# IO.net
KiCad netlist of a schematic drawn in Altium Designer
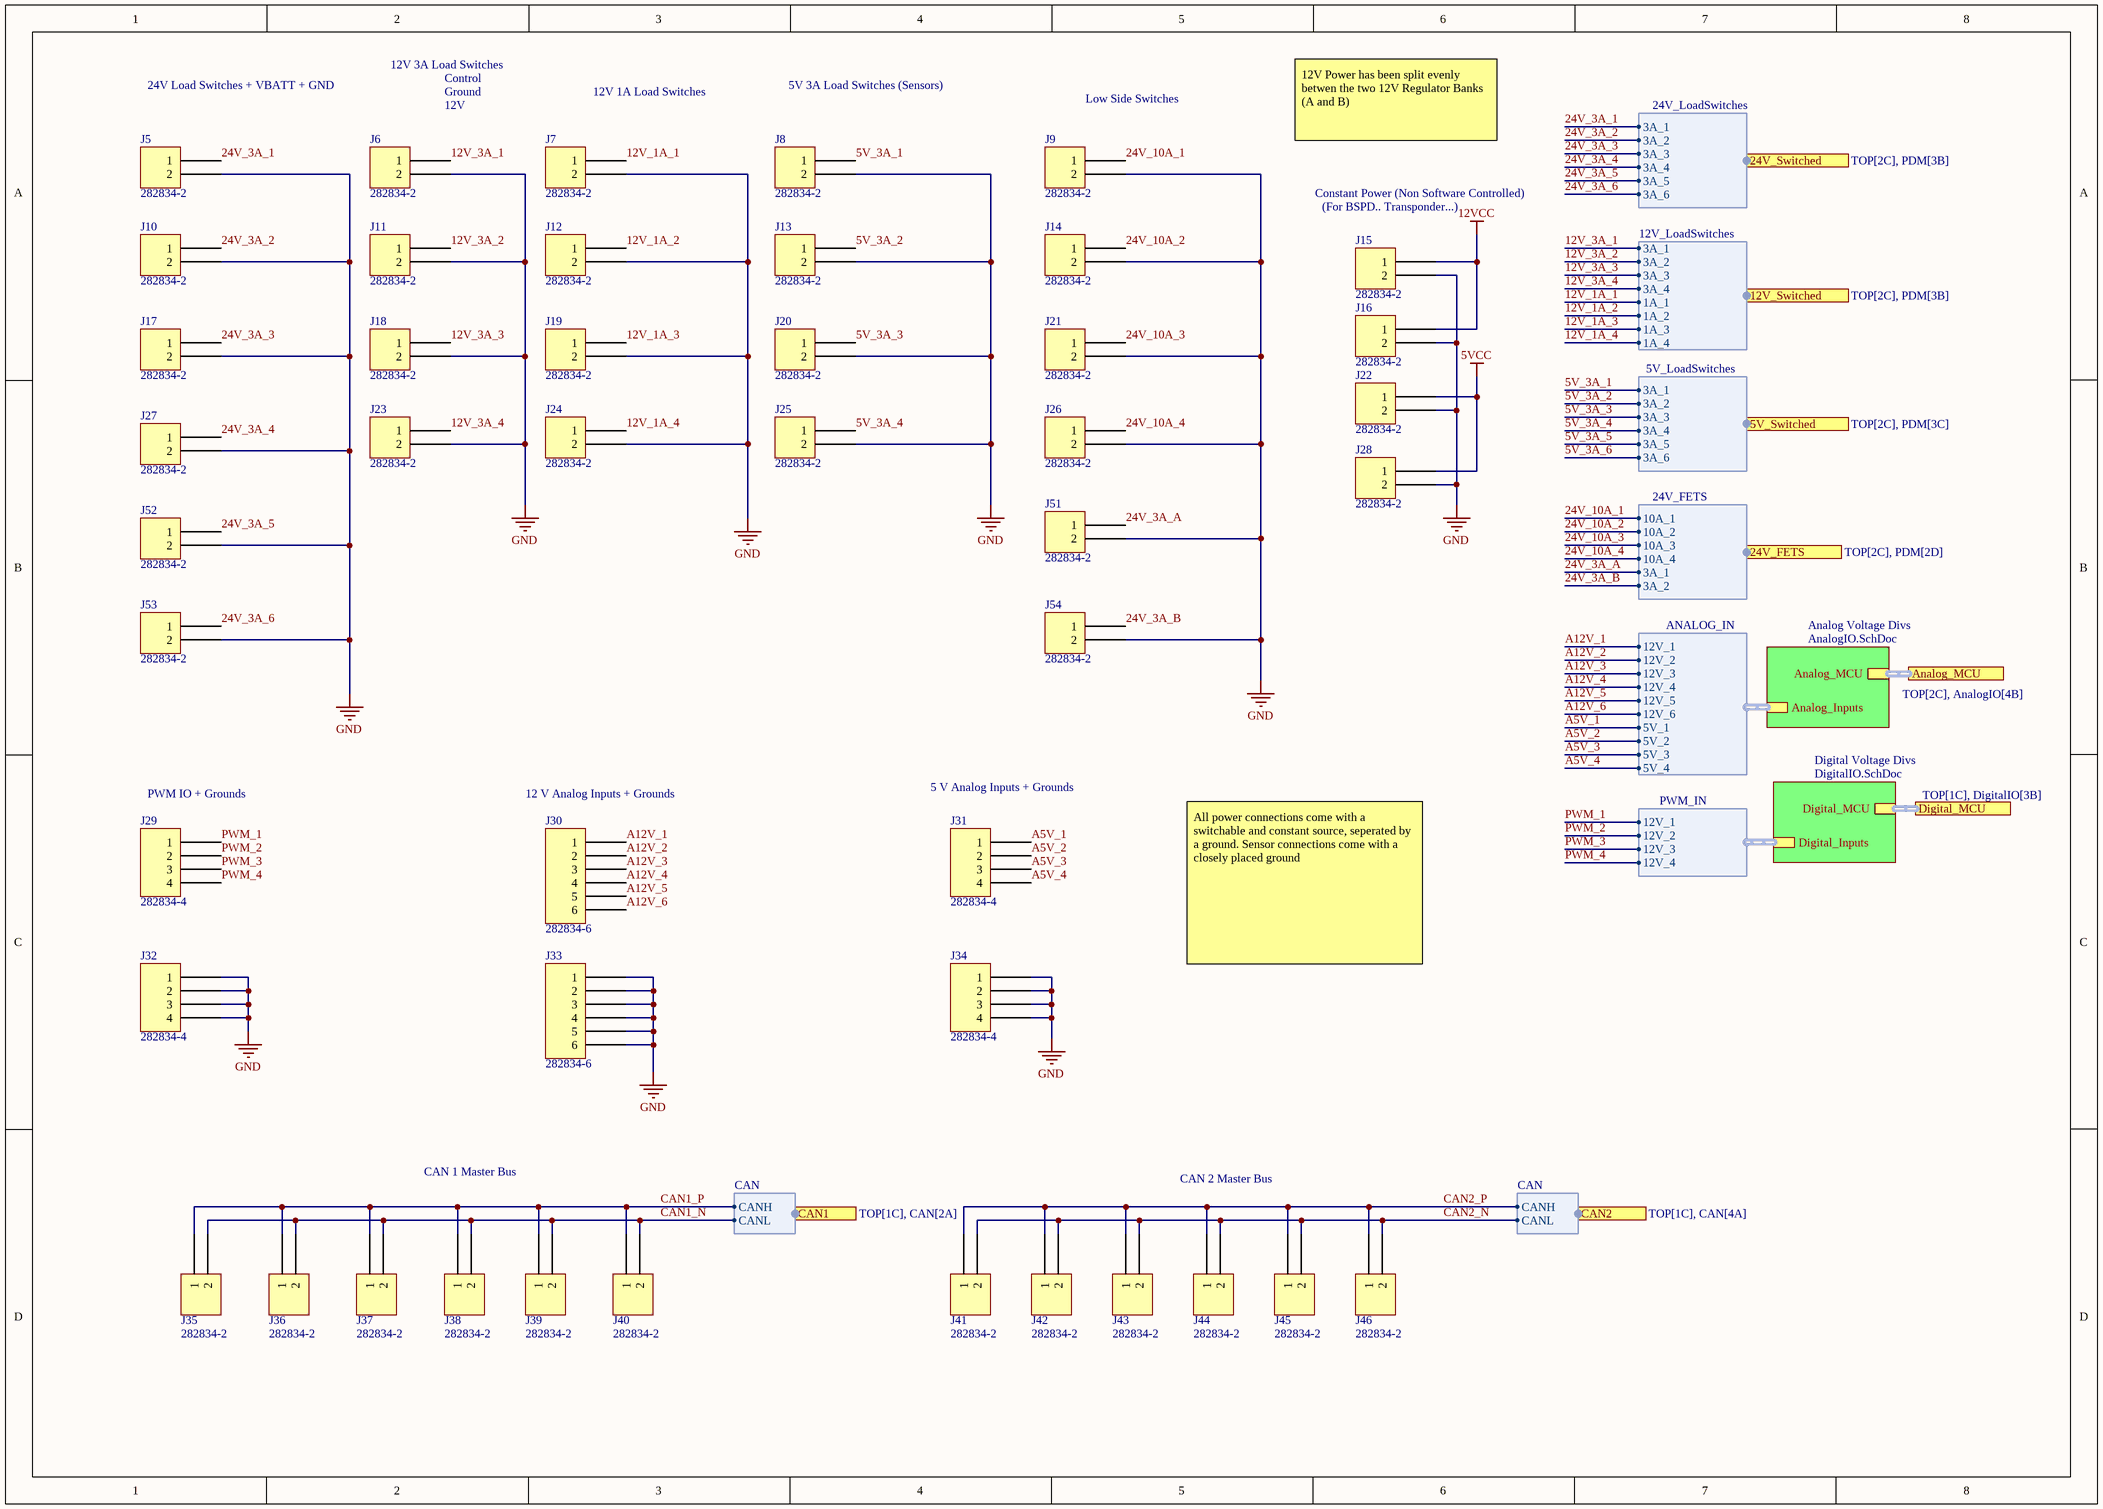
[diagram p0: IO.SchDoc]

(export (version "E")
  (design (tool "Eeschema 10.0.6"))
  (components
    (comp (ref "J5")
      (value "282834-2")
      (footprint "TE 282834-2")
      (description "TERM BLK 2P SIDE ENT 2.54MM PCB")
      (libsource (lib "altium_library") (part "2 Pin"))
    )
    (comp (ref "J6")
      (value "282834-2")
      (footprint "TE 282834-2")
      (description "TERM BLK 2P SIDE ENT 2.54MM PCB")
      (libsource (lib "altium_library") (part "2 Pin"))
    )
    (comp (ref "J7")
      (value "282834-2")
      (footprint "TE 282834-2")
      (description "TERM BLK 2P SIDE ENT 2.54MM PCB")
      (libsource (lib "altium_library") (part "2 Pin"))
    )
    (comp (ref "J8")
      (value "282834-2")
      (footprint "TE 282834-2")
      (description "TERM BLK 2P SIDE ENT 2.54MM PCB")
      (libsource (lib "altium_library") (part "2 Pin"))
    )
    (comp (ref "J9")
      (value "282834-2")
      (footprint "TE 282834-2")
      (description "TERM BLK 2P SIDE ENT 2.54MM PCB")
      (libsource (lib "altium_library") (part "2 Pin"))
    )
    (comp (ref "J10")
      (value "282834-2")
      (footprint "TE 282834-2")
      (description "TERM BLK 2P SIDE ENT 2.54MM PCB")
      (libsource (lib "altium_library") (part "2 Pin"))
    )
    (comp (ref "J11")
      (value "282834-2")
      (footprint "TE 282834-2")
      (description "TERM BLK 2P SIDE ENT 2.54MM PCB")
      (libsource (lib "altium_library") (part "2 Pin"))
    )
    (comp (ref "J12")
      (value "282834-2")
      (footprint "TE 282834-2")
      (description "TERM BLK 2P SIDE ENT 2.54MM PCB")
      (libsource (lib "altium_library") (part "2 Pin"))
    )
    (comp (ref "J13")
      (value "282834-2")
      (footprint "TE 282834-2")
      (description "TERM BLK 2P SIDE ENT 2.54MM PCB")
      (libsource (lib "altium_library") (part "2 Pin"))
    )
    (comp (ref "J14")
      (value "282834-2")
      (footprint "TE 282834-2")
      (description "TERM BLK 2P SIDE ENT 2.54MM PCB")
      (libsource (lib "altium_library") (part "2 Pin"))
    )
    (comp (ref "J15")
      (value "282834-2")
      (footprint "TE 282834-2")
      (description "TERM BLK 2P SIDE ENT 2.54MM PCB")
      (libsource (lib "altium_library") (part "2 Pin"))
    )
    (comp (ref "J16")
      (value "282834-2")
      (footprint "TE 282834-2")
      (description "TERM BLK 2P SIDE ENT 2.54MM PCB")
      (libsource (lib "altium_library") (part "2 Pin"))
    )
    (comp (ref "J17")
      (value "282834-2")
      (footprint "TE 282834-2")
      (description "TERM BLK 2P SIDE ENT 2.54MM PCB")
      (libsource (lib "altium_library") (part "2 Pin"))
    )
    (comp (ref "J18")
      (value "282834-2")
      (footprint "TE 282834-2")
      (description "TERM BLK 2P SIDE ENT 2.54MM PCB")
      (libsource (lib "altium_library") (part "2 Pin"))
    )
    (comp (ref "J19")
      (value "282834-2")
      (footprint "TE 282834-2")
      (description "TERM BLK 2P SIDE ENT 2.54MM PCB")
      (libsource (lib "altium_library") (part "2 Pin"))
    )
    (comp (ref "J20")
      (value "282834-2")
      (footprint "TE 282834-2")
      (description "TERM BLK 2P SIDE ENT 2.54MM PCB")
      (libsource (lib "altium_library") (part "2 Pin"))
    )
    (comp (ref "J21")
      (value "282834-2")
      (footprint "TE 282834-2")
      (description "TERM BLK 2P SIDE ENT 2.54MM PCB")
      (libsource (lib "altium_library") (part "2 Pin"))
    )
    (comp (ref "J22")
      (value "282834-2")
      (footprint "TE 282834-2")
      (description "TERM BLK 2P SIDE ENT 2.54MM PCB")
      (libsource (lib "altium_library") (part "2 Pin"))
    )
    (comp (ref "J23")
      (value "282834-2")
      (footprint "TE 282834-2")
      (description "TERM BLK 2P SIDE ENT 2.54MM PCB")
      (libsource (lib "altium_library") (part "2 Pin"))
    )
    (comp (ref "J24")
      (value "282834-2")
      (footprint "TE 282834-2")
      (description "TERM BLK 2P SIDE ENT 2.54MM PCB")
      (libsource (lib "altium_library") (part "2 Pin"))
    )
    (comp (ref "J25")
      (value "282834-2")
      (footprint "TE 282834-2")
      (description "TERM BLK 2P SIDE ENT 2.54MM PCB")
      (libsource (lib "altium_library") (part "2 Pin"))
    )
    (comp (ref "J26")
      (value "282834-2")
      (footprint "TE 282834-2")
      (description "TERM BLK 2P SIDE ENT 2.54MM PCB")
      (libsource (lib "altium_library") (part "2 Pin"))
    )
    (comp (ref "J27")
      (value "282834-2")
      (footprint "TE 282834-2")
      (description "TERM BLK 2P SIDE ENT 2.54MM PCB")
      (libsource (lib "altium_library") (part "2 Pin"))
    )
    (comp (ref "J28")
      (value "282834-2")
      (footprint "TE 282834-2")
      (description "TERM BLK 2P SIDE ENT 2.54MM PCB")
      (libsource (lib "altium_library") (part "2 Pin"))
    )
    (comp (ref "J29")
      (value "282834-4")
      (footprint "TE 282834-4")
      (description "TERM BLK 4P SIDE ENT 2.54MM PCB")
      (libsource (lib "altium_library") (part "4 Pin"))
    )
    (comp (ref "J30")
      (value "282834-6")
      (footprint "TE 282834-6")
      (description "TERM BLK 6P SIDE ENT 2.54MM PCB")
      (libsource (lib "altium_library") (part "6 Pin"))
    )
    (comp (ref "J31")
      (value "282834-4")
      (footprint "TE 282834-4")
      (description "TERM BLK 4P SIDE ENT 2.54MM PCB")
      (libsource (lib "altium_library") (part "4 Pin"))
    )
    (comp (ref "J32")
      (value "282834-4")
      (footprint "TE 282834-4")
      (description "TERM BLK 4P SIDE ENT 2.54MM PCB")
      (libsource (lib "altium_library") (part "4 Pin"))
    )
    (comp (ref "J33")
      (value "282834-6")
      (footprint "TE 282834-6")
      (description "TERM BLK 6P SIDE ENT 2.54MM PCB")
      (libsource (lib "altium_library") (part "6 Pin"))
    )
    (comp (ref "J34")
      (value "282834-4")
      (footprint "TE 282834-4")
      (description "TERM BLK 4P SIDE ENT 2.54MM PCB")
      (libsource (lib "altium_library") (part "4 Pin"))
    )
    (comp (ref "J35")
      (value "282834-2")
      (footprint "TE 282834-2")
      (description "TERM BLK 2P SIDE ENT 2.54MM PCB")
      (libsource (lib "") (part "2 Pin_1"))
    )
    (comp (ref "J36")
      (value "282834-2")
      (footprint "TE 282834-2")
      (description "TERM BLK 2P SIDE ENT 2.54MM PCB")
      (libsource (lib "") (part "2 Pin_1"))
    )
    (comp (ref "J37")
      (value "282834-2")
      (footprint "TE 282834-2")
      (description "TERM BLK 2P SIDE ENT 2.54MM PCB")
      (libsource (lib "") (part "2 Pin_1"))
    )
    (comp (ref "J38")
      (value "282834-2")
      (footprint "TE 282834-2")
      (description "TERM BLK 2P SIDE ENT 2.54MM PCB")
      (libsource (lib "") (part "2 Pin_1"))
    )
    (comp (ref "J39")
      (value "282834-2")
      (footprint "TE 282834-2")
      (description "TERM BLK 2P SIDE ENT 2.54MM PCB")
      (libsource (lib "") (part "2 Pin_1"))
    )
    (comp (ref "J40")
      (value "282834-2")
      (footprint "TE 282834-2")
      (description "TERM BLK 2P SIDE ENT 2.54MM PCB")
      (libsource (lib "") (part "2 Pin_1"))
    )
    (comp (ref "J41")
      (value "282834-2")
      (footprint "TE 282834-2")
      (description "TERM BLK 2P SIDE ENT 2.54MM PCB")
      (libsource (lib "") (part "2 Pin_1"))
    )
    (comp (ref "J42")
      (value "282834-2")
      (footprint "TE 282834-2")
      (description "TERM BLK 2P SIDE ENT 2.54MM PCB")
      (libsource (lib "") (part "2 Pin_1"))
    )
    (comp (ref "J43")
      (value "282834-2")
      (footprint "TE 282834-2")
      (description "TERM BLK 2P SIDE ENT 2.54MM PCB")
      (libsource (lib "") (part "2 Pin_1"))
    )
    (comp (ref "J44")
      (value "282834-2")
      (footprint "TE 282834-2")
      (description "TERM BLK 2P SIDE ENT 2.54MM PCB")
      (libsource (lib "") (part "2 Pin_1"))
    )
    (comp (ref "J45")
      (value "282834-2")
      (footprint "TE 282834-2")
      (description "TERM BLK 2P SIDE ENT 2.54MM PCB")
      (libsource (lib "") (part "2 Pin_1"))
    )
    (comp (ref "J46")
      (value "282834-2")
      (footprint "TE 282834-2")
      (description "TERM BLK 2P SIDE ENT 2.54MM PCB")
      (libsource (lib "") (part "2 Pin_1"))
    )
    (comp (ref "J51")
      (value "282834-2")
      (footprint "TE 282834-2")
      (description "TERM BLK 2P SIDE ENT 2.54MM PCB")
      (libsource (lib "altium_library") (part "2 Pin"))
    )
    (comp (ref "J52")
      (value "282834-2")
      (footprint "TE 282834-2")
      (description "TERM BLK 2P SIDE ENT 2.54MM PCB")
      (libsource (lib "altium_library") (part "2 Pin"))
    )
    (comp (ref "J53")
      (value "282834-2")
      (footprint "TE 282834-2")
      (description "TERM BLK 2P SIDE ENT 2.54MM PCB")
      (libsource (lib "altium_library") (part "2 Pin"))
    )
    (comp (ref "J54")
      (value "282834-2")
      (footprint "TE 282834-2")
      (description "TERM BLK 2P SIDE ENT 2.54MM PCB")
      (libsource (lib "altium_library") (part "2 Pin"))
    )
  )
  (nets
    (net (code "10") (name "/5V_3A_1") (class "Default")
      (node (ref "J8") (pin "1") (pinfunction "1_1") (pintype "passive"))
    )
    (net (code "11") (name "/5V_3A_2") (class "Default")
      (node (ref "J13") (pin "1") (pinfunction "1_1") (pintype "passive"))
    )
    (net (code "12") (name "/5V_3A_3") (class "Default")
      (node (ref "J20") (pin "1") (pinfunction "1_1") (pintype "passive"))
    )
    (net (code "13") (name "/5V_3A_4") (class "Default")
      (node (ref "J25") (pin "1") (pinfunction "1_1") (pintype "passive"))
    )
    (net (code "16") (name "/12V_1A_1") (class "Default")
      (node (ref "J7") (pin "1") (pinfunction "1_1") (pintype "passive"))
    )
    (net (code "17") (name "/12V_1A_2") (class "Default")
      (node (ref "J12") (pin "1") (pinfunction "1_1") (pintype "passive"))
    )
    (net (code "18") (name "/12V_1A_3") (class "Default")
      (node (ref "J19") (pin "1") (pinfunction "1_1") (pintype "passive"))
    )
    (net (code "19") (name "/12V_1A_4") (class "Default")
      (node (ref "J24") (pin "1") (pinfunction "1_1") (pintype "passive"))
    )
    (net (code "20") (name "/12V_3A_1") (class "Default")
      (node (ref "J6") (pin "1") (pinfunction "1_1") (pintype "passive"))
    )
    (net (code "21") (name "/12V_3A_2") (class "Default")
      (node (ref "J11") (pin "1") (pinfunction "1_1") (pintype "passive"))
    )
    (net (code "22") (name "/12V_3A_3") (class "Default")
      (node (ref "J18") (pin "1") (pinfunction "1_1") (pintype "passive"))
    )
    (net (code "23") (name "/12V_3A_4") (class "Default")
      (node (ref "J23") (pin "1") (pinfunction "1_1") (pintype "passive"))
    )
    (net (code "24") (name "/24V_3A_1") (class "Default")
      (node (ref "J5") (pin "1") (pinfunction "1_1") (pintype "passive"))
    )
    (net (code "25") (name "/24V_3A_2") (class "Default")
      (node (ref "J10") (pin "1") (pinfunction "1_1") (pintype "passive"))
    )
    (net (code "26") (name "/24V_3A_3") (class "Default")
      (node (ref "J17") (pin "1") (pinfunction "1_1") (pintype "passive"))
    )
    (net (code "27") (name "/24V_3A_4") (class "Default")
      (node (ref "J27") (pin "1") (pinfunction "1_1") (pintype "passive"))
    )
    (net (code "28") (name "/24V_3A_5") (class "Default")
      (node (ref "J52") (pin "1") (pinfunction "1_1") (pintype "passive"))
    )
    (net (code "29") (name "/24V_3A_6") (class "Default")
      (node (ref "J53") (pin "1") (pinfunction "1_1") (pintype "passive"))
    )
    (net (code "30") (name "/24V_3A_A") (class "Default")
      (node (ref "J51") (pin "1") (pinfunction "1_1") (pintype "passive"))
    )
    (net (code "31") (name "/24V_3A_B") (class "Default")
      (node (ref "J54") (pin "1") (pinfunction "1_1") (pintype "passive"))
    )
    (net (code "32") (name "/24V_10A_1") (class "Default")
      (node (ref "J9") (pin "1") (pinfunction "1_1") (pintype "passive"))
    )
    (net (code "33") (name "/24V_10A_2") (class "Default")
      (node (ref "J14") (pin "1") (pinfunction "1_1") (pintype "passive"))
    )
    (net (code "34") (name "/24V_10A_3") (class "Default")
      (node (ref "J21") (pin "1") (pinfunction "1_1") (pintype "passive"))
    )
    (net (code "35") (name "/24V_10A_4") (class "Default")
      (node (ref "J26") (pin "1") (pinfunction "1_1") (pintype "passive"))
    )
    (net (code "36") (name "/A5V_1") (class "Default")
      (node (ref "J31") (pin "1") (pinfunction "1_1") (pintype "passive"))
    )
    (net (code "37") (name "/A5V_2") (class "Default")
      (node (ref "J31") (pin "2") (pinfunction "2_2") (pintype "passive"))
    )
    (net (code "38") (name "/A5V_3") (class "Default")
      (node (ref "J31") (pin "3") (pinfunction "3_3") (pintype "passive"))
    )
    (net (code "39") (name "/A5V_4") (class "Default")
      (node (ref "J31") (pin "4") (pinfunction "4_4") (pintype "passive"))
    )
    (net (code "40") (name "/A12V_1") (class "Default")
      (node (ref "J30") (pin "1") (pinfunction "1_1") (pintype "passive"))
    )
    (net (code "41") (name "/A12V_2") (class "Default")
      (node (ref "J30") (pin "2") (pinfunction "2_2") (pintype "passive"))
    )
    (net (code "42") (name "/A12V_3") (class "Default")
      (node (ref "J30") (pin "3") (pinfunction "3_3") (pintype "passive"))
    )
    (net (code "43") (name "/A12V_4") (class "Default")
      (node (ref "J30") (pin "4") (pinfunction "4_4") (pintype "passive"))
    )
    (net (code "44") (name "/A12V_5") (class "Default")
      (node (ref "J30") (pin "5") (pinfunction "5_5") (pintype "passive"))
    )
    (net (code "45") (name "/A12V_6") (class "Default")
      (node (ref "J30") (pin "6") (pinfunction "6_6") (pintype "passive"))
    )
    (net (code "47") (name "/CAN1_N") (class "Default")
      (node (ref "J35") (pin "2") (pinfunction "2_2") (pintype "passive"))
      (node (ref "J36") (pin "2") (pinfunction "2_2") (pintype "passive"))
      (node (ref "J37") (pin "2") (pinfunction "2_2") (pintype "passive"))
      (node (ref "J38") (pin "2") (pinfunction "2_2") (pintype "passive"))
      (node (ref "J39") (pin "2") (pinfunction "2_2") (pintype "passive"))
      (node (ref "J40") (pin "2") (pinfunction "2_2") (pintype "passive"))
    )
    (net (code "48") (name "/CAN1_P") (class "Default")
      (node (ref "J35") (pin "1") (pinfunction "1_1") (pintype "passive"))
      (node (ref "J36") (pin "1") (pinfunction "1_1") (pintype "passive"))
      (node (ref "J37") (pin "1") (pinfunction "1_1") (pintype "passive"))
      (node (ref "J38") (pin "1") (pinfunction "1_1") (pintype "passive"))
      (node (ref "J39") (pin "1") (pinfunction "1_1") (pintype "passive"))
      (node (ref "J40") (pin "1") (pinfunction "1_1") (pintype "passive"))
    )
    (net (code "49") (name "/CAN2_N") (class "Default")
      (node (ref "J41") (pin "2") (pinfunction "2_2") (pintype "passive"))
      (node (ref "J42") (pin "2") (pinfunction "2_2") (pintype "passive"))
      (node (ref "J43") (pin "2") (pinfunction "2_2") (pintype "passive"))
      (node (ref "J44") (pin "2") (pinfunction "2_2") (pintype "passive"))
      (node (ref "J45") (pin "2") (pinfunction "2_2") (pintype "passive"))
      (node (ref "J46") (pin "2") (pinfunction "2_2") (pintype "passive"))
    )
    (net (code "50") (name "/CAN2_P") (class "Default")
      (node (ref "J41") (pin "1") (pinfunction "1_1") (pintype "passive"))
      (node (ref "J42") (pin "1") (pinfunction "1_1") (pintype "passive"))
      (node (ref "J43") (pin "1") (pinfunction "1_1") (pintype "passive"))
      (node (ref "J44") (pin "1") (pinfunction "1_1") (pintype "passive"))
      (node (ref "J45") (pin "1") (pinfunction "1_1") (pintype "passive"))
      (node (ref "J46") (pin "1") (pinfunction "1_1") (pintype "passive"))
    )
    (net (code "52") (name "/PWM_1") (class "Default")
      (node (ref "J29") (pin "1") (pinfunction "1_1") (pintype "passive"))
    )
    (net (code "53") (name "/PWM_2") (class "Default")
      (node (ref "J29") (pin "2") (pinfunction "2_2") (pintype "passive"))
    )
    (net (code "54") (name "/PWM_3") (class "Default")
      (node (ref "J29") (pin "3") (pinfunction "3_3") (pintype "passive"))
    )
    (net (code "55") (name "/PWM_4") (class "Default")
      (node (ref "J29") (pin "4") (pinfunction "4_4") (pintype "passive"))
    )
    (net (code "63") (name "5VCC") (class "Default")
      (node (ref "J22") (pin "1") (pinfunction "1_1") (pintype "passive"))
      (node (ref "J28") (pin "1") (pinfunction "1_1") (pintype "passive"))
    )
    (net (code "64") (name "12VCC") (class "Default")
      (node (ref "J15") (pin "1") (pinfunction "1_1") (pintype "passive"))
      (node (ref "J16") (pin "1") (pinfunction "1_1") (pintype "passive"))
    )
    (net (code "65") (name "GND") (class "Default")
      (node (ref "J10") (pin "2") (pinfunction "2_2") (pintype "passive"))
      (node (ref "J11") (pin "2") (pinfunction "2_2") (pintype "passive"))
      (node (ref "J12") (pin "2") (pinfunction "2_2") (pintype "passive"))
      (node (ref "J13") (pin "2") (pinfunction "2_2") (pintype "passive"))
      (node (ref "J14") (pin "2") (pinfunction "2_2") (pintype "passive"))
      (node (ref "J15") (pin "2") (pinfunction "2_2") (pintype "passive"))
      (node (ref "J16") (pin "2") (pinfunction "2_2") (pintype "passive"))
      (node (ref "J17") (pin "2") (pinfunction "2_2") (pintype "passive"))
      (node (ref "J18") (pin "2") (pinfunction "2_2") (pintype "passive"))
      (node (ref "J19") (pin "2") (pinfunction "2_2") (pintype "passive"))
      (node (ref "J20") (pin "2") (pinfunction "2_2") (pintype "passive"))
      (node (ref "J21") (pin "2") (pinfunction "2_2") (pintype "passive"))
      (node (ref "J22") (pin "2") (pinfunction "2_2") (pintype "passive"))
      (node (ref "J23") (pin "2") (pinfunction "2_2") (pintype "passive"))
      (node (ref "J24") (pin "2") (pinfunction "2_2") (pintype "passive"))
      (node (ref "J25") (pin "2") (pinfunction "2_2") (pintype "passive"))
      (node (ref "J26") (pin "2") (pinfunction "2_2") (pintype "passive"))
      (node (ref "J27") (pin "2") (pinfunction "2_2") (pintype "passive"))
      (node (ref "J28") (pin "2") (pinfunction "2_2") (pintype "passive"))
      (node (ref "J32") (pin "1") (pinfunction "1_1") (pintype "passive"))
      (node (ref "J32") (pin "2") (pinfunction "2_2") (pintype "passive"))
      (node (ref "J32") (pin "3") (pinfunction "3_3") (pintype "passive"))
      (node (ref "J32") (pin "4") (pinfunction "4_4") (pintype "passive"))
      (node (ref "J33") (pin "1") (pinfunction "1_1") (pintype "passive"))
      (node (ref "J33") (pin "2") (pinfunction "2_2") (pintype "passive"))
      (node (ref "J33") (pin "3") (pinfunction "3_3") (pintype "passive"))
      (node (ref "J33") (pin "4") (pinfunction "4_4") (pintype "passive"))
      (node (ref "J33") (pin "5") (pinfunction "5_5") (pintype "passive"))
      (node (ref "J33") (pin "6") (pinfunction "6_6") (pintype "passive"))
      (node (ref "J34") (pin "1") (pinfunction "1_1") (pintype "passive"))
      (node (ref "J34") (pin "2") (pinfunction "2_2") (pintype "passive"))
      (node (ref "J34") (pin "3") (pinfunction "3_3") (pintype "passive"))
      (node (ref "J34") (pin "4") (pinfunction "4_4") (pintype "passive"))
      (node (ref "J5") (pin "2") (pinfunction "2_2") (pintype "passive"))
      (node (ref "J51") (pin "2") (pinfunction "2_2") (pintype "passive"))
      (node (ref "J52") (pin "2") (pinfunction "2_2") (pintype "passive"))
      (node (ref "J53") (pin "2") (pinfunction "2_2") (pintype "passive"))
      (node (ref "J54") (pin "2") (pinfunction "2_2") (pintype "passive"))
      (node (ref "J6") (pin "2") (pinfunction "2_2") (pintype "passive"))
      (node (ref "J7") (pin "2") (pinfunction "2_2") (pintype "passive"))
      (node (ref "J8") (pin "2") (pinfunction "2_2") (pintype "passive"))
      (node (ref "J9") (pin "2") (pinfunction "2_2") (pintype "passive"))
    )
  )
)
